# design.net
KiCad netlist of a schematic drawn in Altium Designer
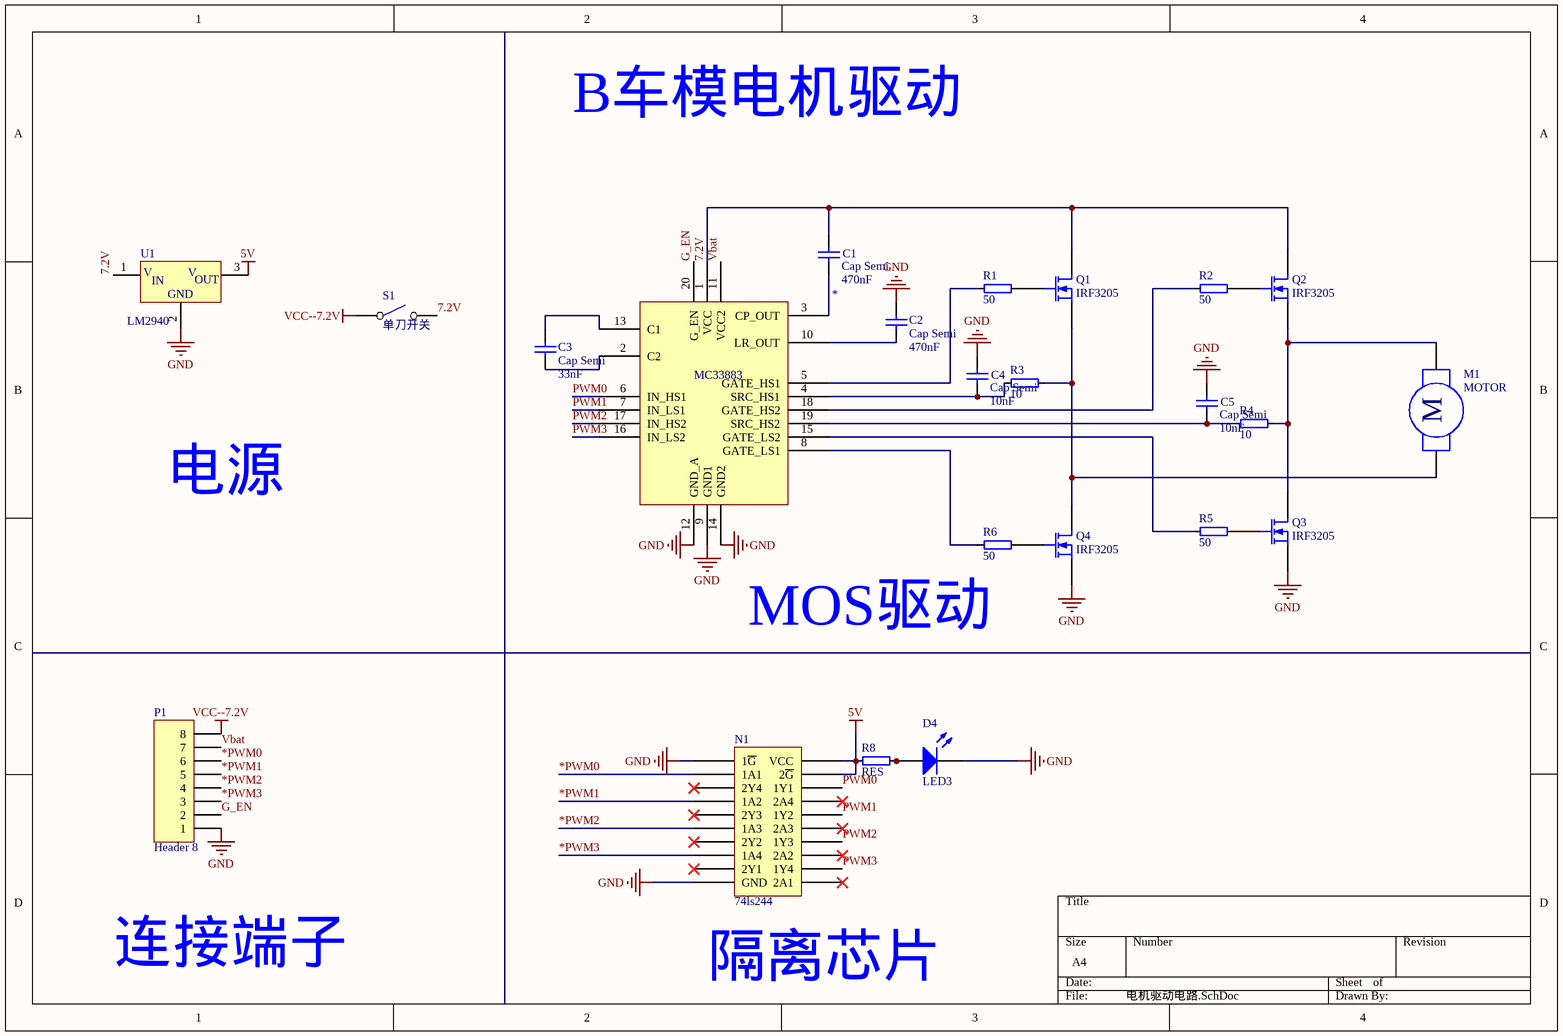
[diagram p0: 电机驱动电路.SchDoc]

(export (version "E")
  (design (tool "Eeschema 10.0.6"))
  (components
    (comp (ref "*")
      (value "MC33883")
      (footprint "20-TERMINAL SOICW")
      (libsource (lib "MC33883") (part "MC33883"))
    )
    (comp (ref "C1")
      (value "Cap Semi")
      (footprint "C1206")
      (description "Capacitor (Semiconductor SIM Model)")
      (fields (field (name "ALTIUM_VALUE") "470nF") (field (name "PUBLISHER") "Altium Limited"))
      (libsource (lib "Miscellaneous Devices") (part "Cap Semi"))
    )
    (comp (ref "C2")
      (value "Cap Semi")
      (footprint "C1206")
      (description "Capacitor (Semiconductor SIM Model)")
      (fields (field (name "ALTIUM_VALUE") "470nF") (field (name "PUBLISHER") "Altium Limited"))
      (libsource (lib "Miscellaneous Devices") (part "Cap Semi"))
    )
    (comp (ref "C3")
      (value "Cap Semi")
      (footprint "C1206")
      (description "Capacitor (Semiconductor SIM Model)")
      (fields (field (name "ALTIUM_VALUE") "33nF") (field (name "PUBLISHER") "Altium Limited"))
      (libsource (lib "Miscellaneous Devices") (part "Cap Semi"))
    )
    (comp (ref "C4")
      (value "Cap Semi")
      (footprint "C1206")
      (description "Capacitor (Semiconductor SIM Model)")
      (fields (field (name "ALTIUM_VALUE") "10nF") (field (name "PUBLISHER") "Altium Limited"))
      (libsource (lib "Miscellaneous Devices") (part "Cap Semi"))
    )
    (comp (ref "C5")
      (value "Cap Semi")
      (footprint "C1206")
      (description "Capacitor (Semiconductor SIM Model)")
      (fields (field (name "ALTIUM_VALUE") "10nF") (field (name "PUBLISHER") "Altium Limited"))
      (libsource (lib "Miscellaneous Devices") (part "Cap Semi"))
    )
    (comp (ref "D4")
      (value "LED3")
      (footprint "3.5X2.8X1.9")
      (description "Typical BLUE SiC LED")
      (fields (field (name "PUBLISHER") "Altium Limited"))
      (libsource (lib "Miscellaneous Devices") (part "LED3"))
    )
    (comp (ref "M1") (value "MOTOR") (footprint "两口插座（绿）") (libsource (lib "单片机及相关") (part "MOTOR")))
    (comp (ref "N1") (value "74ls244") (footprint "DIP20") (libsource (lib "74ls244") (part "74ls244")))
    (comp (ref "P1")
      (value "Header 8")
      (footprint "HDR1X8")
      (description "Header, 8-Pin")
      (fields (field (name "PUBLISHER") "Altium Limited"))
      (libsource (lib "Miscellaneous Connectors") (part "Header 8"))
    )
    (comp (ref "Q1")
      (value "IRF3205")
      (footprint "IRF3205")
      (description "N-Channel MOSFET")
      (fields (field (name "PUBLISHER") "Altium Limited"))
      (libsource (lib "Free Documents") (part "MOSFET-N"))
    )
    (comp (ref "Q2")
      (value "IRF3205")
      (footprint "IRF3205")
      (description "N-Channel MOSFET")
      (fields (field (name "PUBLISHER") "Altium Limited"))
      (libsource (lib "Free Documents") (part "MOSFET-N"))
    )
    (comp (ref "Q3")
      (value "IRF3205")
      (footprint "IRF3205")
      (description "N-Channel MOSFET")
      (fields (field (name "PUBLISHER") "Altium Limited"))
      (libsource (lib "Free Documents") (part "MOSFET-N"))
    )
    (comp (ref "Q4")
      (value "IRF3205")
      (footprint "IRF3205")
      (description "N-Channel MOSFET")
      (fields (field (name "PUBLISHER") "Altium Limited"))
      (libsource (lib "Free Documents") (part "MOSFET-N"))
    )
    (comp (ref "R1") (value "50") (footprint "0805") (libsource (lib "Free Documents") (part "RES")))
    (comp (ref "R2") (value "50") (footprint "0805") (libsource (lib "Free Documents") (part "RES")))
    (comp (ref "R3") (value "10") (footprint "0805") (libsource (lib "Free Documents") (part "RES")))
    (comp (ref "R4") (value "10") (footprint "0805") (libsource (lib "Free Documents") (part "RES")))
    (comp (ref "R5") (value "50") (footprint "0805") (libsource (lib "Free Documents") (part "RES")))
    (comp (ref "R6") (value "50") (footprint "0805") (libsource (lib "Free Documents") (part "RES")))
    (comp (ref "R8") (value "RES") (footprint "0805") (libsource (lib "电阻") (part "RES")))
    (comp (ref "S1") (value "单刀开关") (footprint "DG1282-5.0") (libsource (lib "开关") (part "单刀开关")))
    (comp (ref "U1")
      (value "LM2940")
      (footprint "78XX")
      (description "3-Terminal Positive Voltage Regulator")
      (libsource (lib "78稳压块") (part "78L05"))
    )
  )
  (nets
    (net (code "1") (name "/*PWM0") (class "Default")
      (node (ref "N1") (pin "2") (pinfunction "1A1_2") (pintype "passive"))
      (node (ref "P1") (pin "6") (pinfunction "6_6") (pintype "passive"))
    )
    (net (code "2") (name "/*PWM1") (class "Default")
      (node (ref "N1") (pin "4") (pinfunction "1A2_4") (pintype "passive"))
      (node (ref "P1") (pin "5") (pinfunction "5_5") (pintype "passive"))
    )
    (net (code "3") (name "/*PWM2") (class "Default")
      (node (ref "N1") (pin "6") (pinfunction "1A3_6") (pintype "passive"))
      (node (ref "P1") (pin "4") (pinfunction "4_4") (pintype "passive"))
    )
    (net (code "4") (name "/*PWM3") (class "Default")
      (node (ref "N1") (pin "8") (pinfunction "1A4_8") (pintype "passive"))
      (node (ref "P1") (pin "3") (pinfunction "3_3") (pintype "passive"))
    )
    (net (code "5") (name "/7.2V") (class "Default")
      (node (ref "*") (pin "1") (pinfunction "VCC_1") (pintype "passive"))
      (node (ref "C1") (pin "2") (pinfunction "2_2") (pintype "passive"))
      (node (ref "Q1") (pin "1") (pinfunction "D_1") (pintype "passive"))
      (node (ref "Q2") (pin "1") (pinfunction "D_1") (pintype "passive"))
      (node (ref "S1") (pin "2") (pinfunction "2_2") (pintype "passive"))
      (node (ref "U1") (pin "1") (pinfunction "VIN_1") (pintype "passive"))
    )
    (net (code "7") (name "/G_EN") (class "Default")
      (node (ref "*") (pin "20") (pinfunction "G_EN_20") (pintype "passive"))
      (node (ref "P1") (pin "2") (pinfunction "2_2") (pintype "passive"))
    )
    (net (code "9") (name "/PWM0") (class "Default")
      (node (ref "*") (pin "6") (pinfunction "IN_HS1_6") (pintype "passive"))
      (node (ref "N1") (pin "18") (pinfunction "1Y1_18") (pintype "passive"))
    )
    (net (code "10") (name "/PWM1") (class "Default")
      (node (ref "*") (pin "7") (pinfunction "IN_LS1_7") (pintype "passive"))
      (node (ref "N1") (pin "16") (pinfunction "1Y2_16") (pintype "passive"))
    )
    (net (code "11") (name "/PWM2") (class "Default")
      (node (ref "*") (pin "17") (pinfunction "IN_HS2_17") (pintype "passive"))
      (node (ref "N1") (pin "14") (pinfunction "1Y3_14") (pintype "passive"))
    )
    (net (code "12") (name "/PWM3") (class "Default")
      (node (ref "*") (pin "16") (pinfunction "IN_LS2_16") (pintype "passive"))
      (node (ref "N1") (pin "12") (pinfunction "1Y4_12") (pintype "passive"))
    )
    (net (code "13") (name "/Vbat") (class "Default")
      (node (ref "*") (pin "11") (pinfunction "VCC2_11") (pintype "passive"))
      (node (ref "P1") (pin "7") (pinfunction "7_7") (pintype "passive"))
    )
    (net (code "17") (name "5V") (class "Default")
      (node (ref "N1") (pin "19") (pinfunction "2~{G}_19") (pintype "passive"))
      (node (ref "N1") (pin "20") (pinfunction "VCC_20") (pintype "passive"))
      (node (ref "R8") (pin "1") (pinfunction "1_1") (pintype "passive"))
      (node (ref "U1") (pin "3") (pinfunction "VOUT_3") (pintype "passive"))
    )
    (net (code "18") (name "GND") (class "Default")
      (node (ref "*") (pin "12") (pinfunction "GND_A_12") (pintype "passive"))
      (node (ref "*") (pin "14") (pinfunction "GND2_14") (pintype "passive"))
      (node (ref "*") (pin "9") (pinfunction "GND1_9") (pintype "passive"))
      (node (ref "C2") (pin "1") (pinfunction "1_1") (pintype "passive"))
      (node (ref "C4") (pin "2") (pinfunction "2_2") (pintype "passive"))
      (node (ref "C5") (pin "2") (pinfunction "2_2") (pintype "passive"))
      (node (ref "D4") (pin "2") (pinfunction "K_2") (pintype "passive"))
      (node (ref "N1") (pin "1") (pinfunction "1~{G}_1") (pintype "passive"))
      (node (ref "N1") (pin "10") (pinfunction "GND_10") (pintype "passive"))
      (node (ref "P1") (pin "1") (pinfunction "1_1") (pintype "passive"))
      (node (ref "Q3") (pin "3") (pinfunction "S_3") (pintype "passive"))
      (node (ref "Q4") (pin "3") (pinfunction "S_3") (pintype "passive"))
      (node (ref "U1") (pin "2") (pinfunction "GND_2") (pintype "passive"))
    )
    (net (code "19") (name "Net-(*-C1)") (class "Default")
      (node (ref "*") (pin "13") (pinfunction "C1_13") (pintype "passive"))
      (node (ref "C3") (pin "2") (pinfunction "2_2") (pintype "passive"))
    )
    (net (code "20") (name "Net-(*-C2)") (class "Default")
      (node (ref "*") (pin "2") (pinfunction "C2_2") (pintype "passive"))
      (node (ref "C3") (pin "1") (pinfunction "1_1") (pintype "passive"))
    )
    (net (code "21") (name "Net-(*-CP_OUT)") (class "Default")
      (node (ref "*") (pin "3") (pinfunction "CP_OUT_3") (pintype "passive"))
      (node (ref "C1") (pin "1") (pinfunction "1_1") (pintype "passive"))
    )
    (net (code "22") (name "Net-(*-GATE_HS1)") (class "Default")
      (node (ref "*") (pin "5") (pinfunction "GATE_HS1_5") (pintype "passive"))
      (node (ref "R1") (pin "1") (pinfunction "1_1") (pintype "passive"))
    )
    (net (code "23") (name "Net-(*-GATE_HS2)") (class "Default")
      (node (ref "*") (pin "18") (pinfunction "GATE_HS2_18") (pintype "passive"))
      (node (ref "R2") (pin "1") (pinfunction "1_1") (pintype "passive"))
    )
    (net (code "24") (name "Net-(*-GATE_LS1)") (class "Default")
      (node (ref "*") (pin "8") (pinfunction "GATE_LS1_8") (pintype "passive"))
      (node (ref "R6") (pin "1") (pinfunction "1_1") (pintype "passive"))
    )
    (net (code "25") (name "Net-(*-GATE_LS2)") (class "Default")
      (node (ref "*") (pin "15") (pinfunction "GATE_LS2_15") (pintype "passive"))
      (node (ref "R5") (pin "1") (pinfunction "1_1") (pintype "passive"))
    )
    (net (code "26") (name "Net-(*-LR_OUT)") (class "Default")
      (node (ref "*") (pin "10") (pinfunction "LR_OUT_10") (pintype "passive"))
      (node (ref "C2") (pin "2") (pinfunction "2_2") (pintype "passive"))
    )
    (net (code "27") (name "Net-(*-SRC_HS1)") (class "Default")
      (node (ref "*") (pin "4") (pinfunction "SRC_HS1_4") (pintype "passive"))
      (node (ref "C4") (pin "1") (pinfunction "1_1") (pintype "passive"))
      (node (ref "R3") (pin "1") (pinfunction "1_1") (pintype "passive"))
    )
    (net (code "28") (name "Net-(*-SRC_HS2)") (class "Default")
      (node (ref "*") (pin "19") (pinfunction "SRC_HS2_19") (pintype "passive"))
      (node (ref "C5") (pin "1") (pinfunction "1_1") (pintype "passive"))
      (node (ref "R4") (pin "1") (pinfunction "1_1") (pintype "passive"))
    )
    (net (code "29") (name "Net-(D4-A)") (class "Default")
      (node (ref "D4") (pin "1") (pinfunction "A_1") (pintype "passive"))
      (node (ref "R8") (pin "2") (pinfunction "2_2") (pintype "passive"))
    )
    (net (code "30") (name "Net-(Q1-G)") (class "Default")
      (node (ref "Q1") (pin "2") (pinfunction "G_2") (pintype "passive"))
      (node (ref "R1") (pin "2") (pinfunction "2_2") (pintype "passive"))
    )
    (net (code "31") (name "Net-(Q1-S)") (class "Default")
      (node (ref "M1") (pin "2") (pinfunction "2_2") (pintype "passive"))
      (node (ref "Q1") (pin "3") (pinfunction "S_3") (pintype "passive"))
      (node (ref "Q4") (pin "1") (pinfunction "D_1") (pintype "passive"))
      (node (ref "R3") (pin "2") (pinfunction "2_2") (pintype "passive"))
    )
    (net (code "32") (name "Net-(Q2-G)") (class "Default")
      (node (ref "Q2") (pin "2") (pinfunction "G_2") (pintype "passive"))
      (node (ref "R2") (pin "2") (pinfunction "2_2") (pintype "passive"))
    )
    (net (code "33") (name "Net-(Q2-S)") (class "Default")
      (node (ref "M1") (pin "1") (pinfunction "1_1") (pintype "passive"))
      (node (ref "Q2") (pin "3") (pinfunction "S_3") (pintype "passive"))
      (node (ref "Q3") (pin "1") (pinfunction "D_1") (pintype "passive"))
      (node (ref "R4") (pin "2") (pinfunction "2_2") (pintype "passive"))
    )
    (net (code "34") (name "Net-(Q3-G)") (class "Default")
      (node (ref "Q3") (pin "2") (pinfunction "G_2") (pintype "passive"))
      (node (ref "R5") (pin "2") (pinfunction "2_2") (pintype "passive"))
    )
    (net (code "35") (name "Net-(Q4-G)") (class "Default")
      (node (ref "Q4") (pin "2") (pinfunction "G_2") (pintype "passive"))
      (node (ref "R6") (pin "2") (pinfunction "2_2") (pintype "passive"))
    )
    (net (code "36") (name "VCC--7.2V") (class "Default")
      (node (ref "P1") (pin "8") (pinfunction "8_8") (pintype "passive"))
      (node (ref "S1") (pin "1") (pinfunction "1_1") (pintype "passive"))
    )
    (net (code "37") (name "unconnected-(N1-2A1-Pad11)") (class "Default")
      (node (ref "N1") (pin "11") (pinfunction "2A1_11") (pintype "passive+no_connect"))
    )
    (net (code "38") (name "unconnected-(N1-2A2-Pad13)") (class "Default")
      (node (ref "N1") (pin "13") (pinfunction "2A2_13") (pintype "passive+no_connect"))
    )
    (net (code "39") (name "unconnected-(N1-2A3-Pad15)") (class "Default")
      (node (ref "N1") (pin "15") (pinfunction "2A3_15") (pintype "passive+no_connect"))
    )
    (net (code "40") (name "unconnected-(N1-2A4-Pad17)") (class "Default")
      (node (ref "N1") (pin "17") (pinfunction "2A4_17") (pintype "passive+no_connect"))
    )
    (net (code "41") (name "unconnected-(N1-2Y1-Pad9)") (class "Default")
      (node (ref "N1") (pin "9") (pinfunction "2Y1_9") (pintype "passive+no_connect"))
    )
    (net (code "42") (name "unconnected-(N1-2Y2-Pad7)") (class "Default")
      (node (ref "N1") (pin "7") (pinfunction "2Y2_7") (pintype "passive+no_connect"))
    )
    (net (code "43") (name "unconnected-(N1-2Y3-Pad5)") (class "Default")
      (node (ref "N1") (pin "5") (pinfunction "2Y3_5") (pintype "passive+no_connect"))
    )
    (net (code "44") (name "unconnected-(N1-2Y4-Pad3)") (class "Default")
      (node (ref "N1") (pin "3") (pinfunction "2Y4_3") (pintype "passive+no_connect"))
    )
  )
)
